# Rotary_Pot.net
KiCad netlist of a schematic drawn in Altium Designer
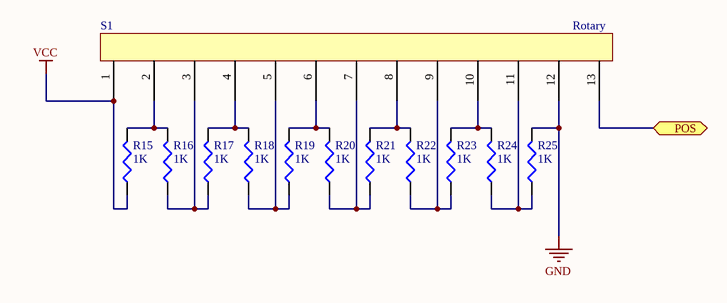
[diagram p0: Rotary_Pot.SchDoc]

(export (version "E")
  (design (tool "Eeschema 10.0.6"))
  (components
    (comp (ref "R15")
      (value "1K")
      (footprint "J1-0603")
      (description "Resistor")
      (fields (field (name "Comment") "Res3") (field (name "PUBLISHER") "Altium Limited"))
      (libsource (lib "Miscellaneous Devices") (part "Res3"))
    )
    (comp (ref "R16")
      (value "1K")
      (footprint "J1-0603")
      (description "Resistor")
      (fields (field (name "Comment") "Res3") (field (name "PUBLISHER") "Altium Limited"))
      (libsource (lib "Miscellaneous Devices") (part "Res3"))
    )
    (comp (ref "R17")
      (value "1K")
      (footprint "J1-0603")
      (description "Resistor")
      (fields (field (name "Comment") "Res3") (field (name "PUBLISHER") "Altium Limited"))
      (libsource (lib "Miscellaneous Devices") (part "Res3"))
    )
    (comp (ref "R18")
      (value "1K")
      (footprint "J1-0603")
      (description "Resistor")
      (fields (field (name "Comment") "Res3") (field (name "PUBLISHER") "Altium Limited"))
      (libsource (lib "Miscellaneous Devices") (part "Res3"))
    )
    (comp (ref "R19")
      (value "1K")
      (footprint "J1-0603")
      (description "Resistor")
      (fields (field (name "Comment") "Res3") (field (name "PUBLISHER") "Altium Limited"))
      (libsource (lib "Miscellaneous Devices") (part "Res3"))
    )
    (comp (ref "R20")
      (value "1K")
      (footprint "J1-0603")
      (description "Resistor")
      (fields (field (name "Comment") "Res3") (field (name "PUBLISHER") "Altium Limited"))
      (libsource (lib "Miscellaneous Devices") (part "Res3"))
    )
    (comp (ref "R21")
      (value "1K")
      (footprint "J1-0603")
      (description "Resistor")
      (fields (field (name "Comment") "Res3") (field (name "PUBLISHER") "Altium Limited"))
      (libsource (lib "Miscellaneous Devices") (part "Res3"))
    )
    (comp (ref "R22")
      (value "1K")
      (footprint "J1-0603")
      (description "Resistor")
      (fields (field (name "Comment") "Res3") (field (name "PUBLISHER") "Altium Limited"))
      (libsource (lib "Miscellaneous Devices") (part "Res3"))
    )
    (comp (ref "R23")
      (value "1K")
      (footprint "J1-0603")
      (description "Resistor")
      (fields (field (name "Comment") "Res3") (field (name "PUBLISHER") "Altium Limited"))
      (libsource (lib "Miscellaneous Devices") (part "Res3"))
    )
    (comp (ref "R24")
      (value "1K")
      (footprint "J1-0603")
      (description "Resistor")
      (fields (field (name "Comment") "Res3") (field (name "PUBLISHER") "Altium Limited"))
      (libsource (lib "Miscellaneous Devices") (part "Res3"))
    )
    (comp (ref "R25")
      (value "1K")
      (footprint "J1-0603")
      (description "Resistor")
      (fields (field (name "Comment") "Res3") (field (name "PUBLISHER") "Altium Limited"))
      (libsource (lib "Miscellaneous Devices") (part "Res3"))
    )
    (comp (ref "S1") (value "Rotary") (footprint "Rotary") (libsource (lib "IntLibrary") (part "Rotary")))
  )
  (nets
    (net (code "1") (name "/POS") (class "Default")
      (node (ref "S1") (pin "13") (pinfunction "13_13") (pintype "passive"))
    )
    (net (code "2") (name "GND") (class "Default")
      (node (ref "R25") (pin "2") (pinfunction "2_2") (pintype "passive"))
      (node (ref "S1") (pin "12") (pintype "passive"))
    )
    (net (code "3") (name "Net-(R15-Pad2)") (class "Default")
      (node (ref "R15") (pin "2") (pinfunction "2_2") (pintype "passive"))
      (node (ref "R16") (pin "2") (pinfunction "2_2") (pintype "passive"))
      (node (ref "S1") (pin "2") (pintype "passive"))
    )
    (net (code "4") (name "Net-(R16-Pad1)") (class "Default")
      (node (ref "R16") (pin "1") (pinfunction "1_1") (pintype "passive"))
      (node (ref "R17") (pin "1") (pinfunction "1_1") (pintype "passive"))
      (node (ref "S1") (pin "3") (pintype "passive"))
    )
    (net (code "5") (name "Net-(R17-Pad2)") (class "Default")
      (node (ref "R17") (pin "2") (pinfunction "2_2") (pintype "passive"))
      (node (ref "R18") (pin "2") (pinfunction "2_2") (pintype "passive"))
      (node (ref "S1") (pin "4") (pintype "passive"))
    )
    (net (code "6") (name "Net-(R18-Pad1)") (class "Default")
      (node (ref "R18") (pin "1") (pinfunction "1_1") (pintype "passive"))
      (node (ref "R19") (pin "1") (pinfunction "1_1") (pintype "passive"))
      (node (ref "S1") (pin "5") (pintype "passive"))
    )
    (net (code "7") (name "Net-(R19-Pad2)") (class "Default")
      (node (ref "R19") (pin "2") (pinfunction "2_2") (pintype "passive"))
      (node (ref "R20") (pin "2") (pinfunction "2_2") (pintype "passive"))
      (node (ref "S1") (pin "6") (pintype "passive"))
    )
    (net (code "8") (name "Net-(R20-Pad1)") (class "Default")
      (node (ref "R20") (pin "1") (pinfunction "1_1") (pintype "passive"))
      (node (ref "R21") (pin "1") (pinfunction "1_1") (pintype "passive"))
      (node (ref "S1") (pin "7") (pintype "passive"))
    )
    (net (code "9") (name "Net-(R21-Pad2)") (class "Default")
      (node (ref "R21") (pin "2") (pinfunction "2_2") (pintype "passive"))
      (node (ref "R22") (pin "2") (pinfunction "2_2") (pintype "passive"))
      (node (ref "S1") (pin "8") (pintype "passive"))
    )
    (net (code "10") (name "Net-(R22-Pad1)") (class "Default")
      (node (ref "R22") (pin "1") (pinfunction "1_1") (pintype "passive"))
      (node (ref "R23") (pin "1") (pinfunction "1_1") (pintype "passive"))
      (node (ref "S1") (pin "9") (pintype "passive"))
    )
    (net (code "11") (name "Net-(R23-Pad2)") (class "Default")
      (node (ref "R23") (pin "2") (pinfunction "2_2") (pintype "passive"))
      (node (ref "R24") (pin "2") (pinfunction "2_2") (pintype "passive"))
      (node (ref "S1") (pin "10") (pintype "passive"))
    )
    (net (code "12") (name "Net-(R24-Pad1)") (class "Default")
      (node (ref "R24") (pin "1") (pinfunction "1_1") (pintype "passive"))
      (node (ref "R25") (pin "1") (pinfunction "1_1") (pintype "passive"))
      (node (ref "S1") (pin "11") (pintype "passive"))
    )
    (net (code "13") (name "VCC") (class "Default")
      (node (ref "R15") (pin "1") (pinfunction "1_1") (pintype "passive"))
      (node (ref "S1") (pin "1") (pintype "passive"))
    )
  )
)
